# 12_uSD.net
KiCad netlist of a schematic drawn in Altium Designer
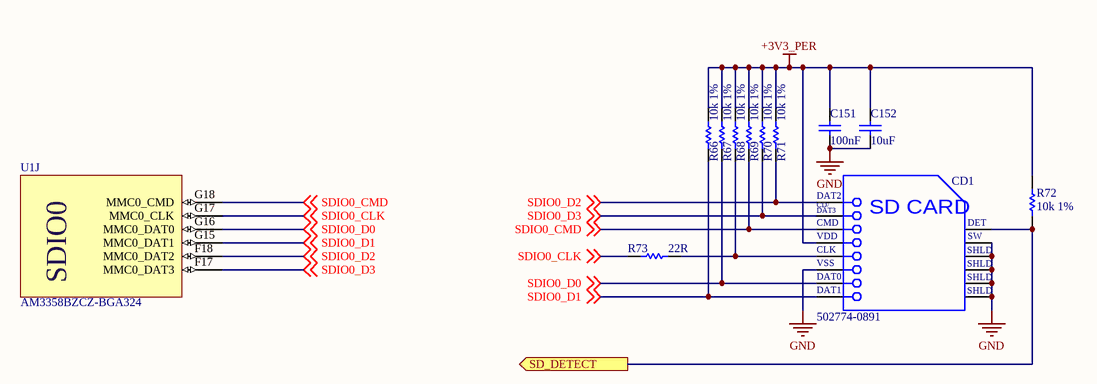
[diagram p0: 12. uSD.SchDoc]

(export (version "E")
  (design (tool "Eeschema 10.0.6"))
  (components
    (comp (ref "C151")
      (value "100nF")
      (footprint "CAPC1005X55X25LL05T10")
      (description "Chip Capacitor, 0.1 uF, +/- 10%, 16 V, -55 to 125 degC, 0402 (1005 Metric), RoHS, Tape and Reel")
      (fields (field (name "VOLTAGE") "16V") (field (name "TOLERANCE") "10%"))
      (libsource (lib "Altium Content Vault") (part "CAP-NP-2"))
    )
    (comp (ref "C152")
      (value "10uF")
      (footprint "CAPC1608X90X35NL10T15")
      (description "Chip Capacitor, 10 uF, +/- 10%, 6.3 V, -55 to 125 degC, 0603 (1608 Metric), RoHS, Tape and Reel")
      (fields (field (name "PART NUMBER") "GRM188R60J106ME47D") (field (name "MANUFACTURER") "Murata"))
      (libsource (lib "Altium Content Vault") (part "CAP"))
    )
    (comp (ref "CD1")
      (value "502774-0891")
      (footprint "MOLX-502774-0891_V")
      (description "Micro SD Memory Card Connector, 0.5 A, 10 V (DC), -25 to 85 degC, 8-Pin SMT, RoHS, Tape and Reel")
      (fields (field (name "MANUFACTURER") "Molex"))
      (libsource (lib "Altium Content Vault") (part "CN-SD-8-2SW-4S_B"))
    )
    (comp (ref "R66")
      (value "10k 1%")
      (footprint "RESC1005X40X25LL05T05")
      (description "10k 0.063W 1% 0402 (1005 Metric)  SMD")
      (fields (field (name "MANUFACTURER") "Vishay Dale") (field (name "PART NUMBER") "CRCW040210K0FKED"))
      (libsource (lib "AM3358_DEV_BOARD") (part "RES"))
    )
    (comp (ref "R67")
      (value "10k 1%")
      (footprint "RESC1005X40X25LL05T05")
      (description "10k 0.063W 1% 0402 (1005 Metric)  SMD")
      (fields (field (name "MANUFACTURER") "Vishay Dale") (field (name "PART NUMBER") "CRCW040210K0FKED"))
      (libsource (lib "AM3358_DEV_BOARD") (part "RES"))
    )
    (comp (ref "R68")
      (value "10k 1%")
      (footprint "RESC1005X40X25LL05T05")
      (description "10k 0.063W 1% 0402 (1005 Metric)  SMD")
      (fields (field (name "MANUFACTURER") "Vishay Dale") (field (name "PART NUMBER") "CRCW040210K0FKED"))
      (libsource (lib "AM3358_DEV_BOARD") (part "RES"))
    )
    (comp (ref "R69")
      (value "10k 1%")
      (footprint "RESC1005X40X25LL05T05")
      (description "10k 0.063W 1% 0402 (1005 Metric)  SMD")
      (fields (field (name "MANUFACTURER") "Vishay Dale") (field (name "PART NUMBER") "CRCW040210K0FKED"))
      (libsource (lib "AM3358_DEV_BOARD") (part "RES"))
    )
    (comp (ref "R70")
      (value "10k 1%")
      (footprint "RESC1005X40X25LL05T05")
      (description "10k 0.063W 1% 0402 (1005 Metric)  SMD")
      (fields (field (name "MANUFACTURER") "Vishay Dale") (field (name "PART NUMBER") "CRCW040210K0FKED"))
      (libsource (lib "AM3358_DEV_BOARD") (part "RES"))
    )
    (comp (ref "R71")
      (value "10k 1%")
      (footprint "RESC1005X40X25LL05T05")
      (description "10k 0.063W 1% 0402 (1005 Metric)  SMD")
      (fields (field (name "MANUFACTURER") "Vishay Dale") (field (name "PART NUMBER") "CRCW040210K0FKED"))
      (libsource (lib "AM3358_DEV_BOARD") (part "RES"))
    )
    (comp (ref "R72")
      (value "10k 1%")
      (footprint "RESC1005X40X25LL05T05")
      (description "10k 0.063W 1% 0402 (1005 Metric)  SMD")
      (fields (field (name "MANUFACTURER") "Vishay Dale") (field (name "PART NUMBER") "CRCW040210K0FKED"))
      (libsource (lib "AM3358_DEV_BOARD") (part "RES"))
    )
    (comp (ref "R73")
      (value "22R")
      (footprint "RESC1005X40X25LL05T05")
      (description "Chip Resistor, 22 Ohm, +/- 1%, 0.1 W, -55 to 155 degC, 0402 (1005 Metric), RoHS, Tape and Reel")
      (fields (field (name "PARTNUMBER") "ERJ-2RKF22R0X") (field (name "TOLERANCE") "1%"))
      (libsource (lib "AM3358_DEV_BOARD") (part "RES-2"))
    )
    (comp (ref "U1")
      (value "AM3358BZCZ-BGA324")
      (footprint "TI-ZCZ324")
      (libsource (lib "SyTungNguyen") (part "AM3358BZCZ100"))
    )
  )
  (nets
    (net (code "1") (name "+3V3_PER") (class "Default")
      (node (ref "C151") (pin "2") (pinfunction "2_2") (pintype "passive"))
      (node (ref "C152") (pin "2") (pinfunction "2_2") (pintype "passive"))
      (node (ref "CD1") (pin "4") (pinfunction "VDD_4") (pintype "passive"))
      (node (ref "R66") (pin "2") (pinfunction "2_2") (pintype "passive"))
      (node (ref "R67") (pin "2") (pinfunction "2_2") (pintype "passive"))
      (node (ref "R68") (pin "2") (pinfunction "2_2") (pintype "passive"))
      (node (ref "R69") (pin "2") (pinfunction "2_2") (pintype "passive"))
      (node (ref "R70") (pin "2") (pinfunction "2_2") (pintype "passive"))
      (node (ref "R71") (pin "2") (pinfunction "2_2") (pintype "passive"))
      (node (ref "R72") (pin "2") (pinfunction "2_2") (pintype "passive"))
    )
    (net (code "2") (name "/SD_DETECT") (class "Default")
      (node (ref "CD1") (pin "9") (pinfunction "DETECT_9") (pintype "passive"))
      (node (ref "R72") (pin "1") (pinfunction "1_1") (pintype "passive"))
    )
    (net (code "3") (name "GND") (class "Default")
      (node (ref "C151") (pin "1") (pinfunction "1_1") (pintype "passive"))
      (node (ref "C152") (pin "1") (pinfunction "1_1") (pintype "passive"))
      (node (ref "CD1") (pin "10") (pinfunction "SWITCH_10") (pintype "passive"))
      (node (ref "CD1") (pin "11") (pinfunction "SHLD_11") (pintype "passive"))
      (node (ref "CD1") (pin "12") (pinfunction "SHLD_12") (pintype "passive"))
      (node (ref "CD1") (pin "13") (pinfunction "SHLD_13") (pintype "passive"))
      (node (ref "CD1") (pin "14") (pinfunction "SHLD_14") (pintype "passive"))
      (node (ref "CD1") (pin "6") (pinfunction "VSS_6") (pintype "passive"))
    )
    (net (code "4") (name "Net-(CD1-CLK)") (class "Default")
      (node (ref "CD1") (pin "5") (pinfunction "CLK_5") (pintype "passive"))
      (node (ref "R68") (pin "1") (pinfunction "1_1") (pintype "passive"))
      (node (ref "R73") (pin "2") (pinfunction "2_2") (pintype "passive"))
    )
    (net (code "5") (name "SDIO0_CLK") (class "Default")
      (node (ref "R73") (pin "1") (pinfunction "1_1") (pintype "passive"))
      (node (ref "U1") (pin "G17") (pinfunction "MMC0_CLK_G17") (pintype "bidirectional"))
    )
    (net (code "6") (name "SDIO0_CMD") (class "Default")
      (node (ref "CD1") (pin "3") (pinfunction "CMD_3") (pintype "passive"))
      (node (ref "R69") (pin "1") (pinfunction "1_1") (pintype "passive"))
      (node (ref "U1") (pin "G18") (pinfunction "MMC0_CMD_G18") (pintype "bidirectional"))
    )
    (net (code "7") (name "SDIO0_D0") (class "Default")
      (node (ref "CD1") (pin "7") (pinfunction "DAT0_7") (pintype "passive"))
      (node (ref "R67") (pin "1") (pinfunction "1_1") (pintype "passive"))
      (node (ref "U1") (pin "G16") (pinfunction "MMC0_DAT0_G16") (pintype "bidirectional"))
    )
    (net (code "8") (name "SDIO0_D1") (class "Default")
      (node (ref "CD1") (pin "8") (pinfunction "DAT1_8") (pintype "passive"))
      (node (ref "R66") (pin "1") (pinfunction "1_1") (pintype "passive"))
      (node (ref "U1") (pin "G15") (pinfunction "MMC0_DAT1_G15") (pintype "bidirectional"))
    )
    (net (code "9") (name "SDIO0_D2") (class "Default")
      (node (ref "CD1") (pin "1") (pinfunction "DAT2_1") (pintype "passive"))
      (node (ref "R71") (pin "1") (pinfunction "1_1") (pintype "passive"))
      (node (ref "U1") (pin "F18") (pinfunction "MMC0_DAT2_F18") (pintype "bidirectional"))
    )
    (net (code "10") (name "SDIO0_D3") (class "Default")
      (node (ref "CD1") (pin "2") (pinfunction "CD/DAT3_2") (pintype "passive"))
      (node (ref "R70") (pin "1") (pinfunction "1_1") (pintype "passive"))
      (node (ref "U1") (pin "F17") (pinfunction "MMC0_DAT3_F17") (pintype "bidirectional"))
    )
  )
)
